# Mainboard.net
KiCad netlist of a schematic drawn in EAGLE
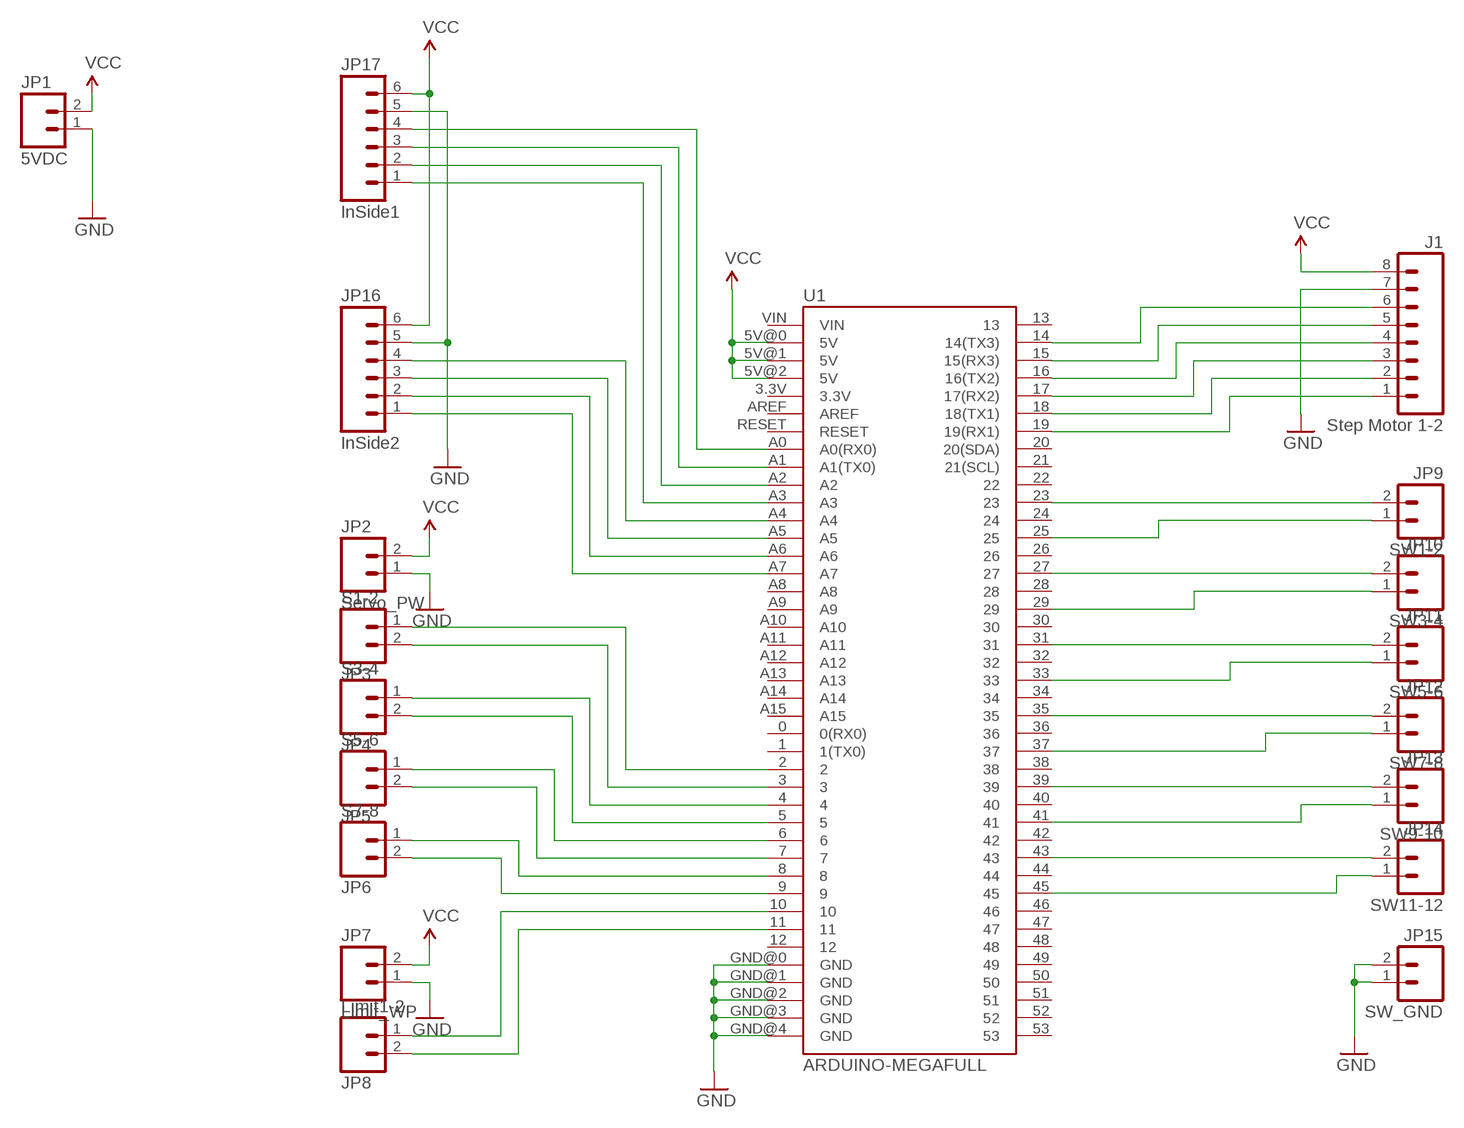
[diagram p0: schematic, sheet 1]

(export (version "E")
  (design (tool "Eeschema 10.0.6"))
  (components
    (comp (ref "J1")
      (value "Step Motor 1-2")
      (footprint "eagle-import:1X08_LONGPADS")
      (libsource (lib "eagle-import") (part "M08LONGPADS"))
    )
    (comp (ref "JP1")
      (value "5VDC")
      (footprint "eagle-import:SCREWTERMINAL-5MM-2")
      (libsource (lib "eagle-import") (part "M025MM"))
    )
    (comp (ref "JP2")
      (value "Servo_PW")
      (footprint "eagle-import:SCREWTERMINAL-5MM-2")
      (libsource (lib "eagle-import") (part "M025MM"))
    )
    (comp (ref "JP3")
      (value "S1-2")
      (footprint "eagle-import:SCREWTERMINAL-5MM-2")
      (libsource (lib "eagle-import") (part "M025MM"))
    )
    (comp (ref "JP4")
      (value "S3-4")
      (footprint "eagle-import:SCREWTERMINAL-5MM-2")
      (libsource (lib "eagle-import") (part "M025MM"))
    )
    (comp (ref "JP5")
      (value "S5-6")
      (footprint "eagle-import:SCREWTERMINAL-5MM-2")
      (libsource (lib "eagle-import") (part "M025MM"))
    )
    (comp (ref "JP6")
      (value "S7-8")
      (footprint "eagle-import:SCREWTERMINAL-5MM-2")
      (libsource (lib "eagle-import") (part "M025MM"))
    )
    (comp (ref "JP7")
      (value "Limit_WP")
      (footprint "eagle-import:SCREWTERMINAL-5MM-2")
      (libsource (lib "eagle-import") (part "M025MM"))
    )
    (comp (ref "JP8")
      (value "Limit1-2")
      (footprint "eagle-import:SCREWTERMINAL-5MM-2")
      (libsource (lib "eagle-import") (part "M025MM"))
    )
    (comp (ref "JP9")
      (value "SW1-2")
      (footprint "eagle-import:SCREWTERMINAL-5MM-2")
      (libsource (lib "eagle-import") (part "M025MM"))
    )
    (comp (ref "JP10")
      (value "SW3-4")
      (footprint "eagle-import:SCREWTERMINAL-5MM-2")
      (libsource (lib "eagle-import") (part "M025MM"))
    )
    (comp (ref "JP11")
      (value "SW5-6")
      (footprint "eagle-import:SCREWTERMINAL-5MM-2")
      (libsource (lib "eagle-import") (part "M025MM"))
    )
    (comp (ref "JP12")
      (value "SW7-8")
      (footprint "eagle-import:SCREWTERMINAL-5MM-2")
      (libsource (lib "eagle-import") (part "M025MM"))
    )
    (comp (ref "JP13")
      (value "SW9-10")
      (footprint "eagle-import:SCREWTERMINAL-5MM-2")
      (libsource (lib "eagle-import") (part "M025MM"))
    )
    (comp (ref "JP14")
      (value "SW11-12")
      (footprint "eagle-import:SCREWTERMINAL-5MM-2")
      (libsource (lib "eagle-import") (part "M025MM"))
    )
    (comp (ref "JP15")
      (value "SW_GND")
      (footprint "eagle-import:SCREWTERMINAL-5MM-2")
      (libsource (lib "eagle-import") (part "M025MM"))
    )
    (comp (ref "JP16")
      (value "InSide2")
      (footprint "eagle-import:1X06_LONGPADS")
      (libsource (lib "eagle-import") (part "M06LONGPADS"))
    )
    (comp (ref "JP17")
      (value "InSide1")
      (footprint "eagle-import:1X06_LONGPADS")
      (libsource (lib "eagle-import") (part "M06LONGPADS"))
    )
    (comp (ref "U1")
      (value "ARDUINO-MEGAFULL")
      (footprint "eagle-import:ARDUINO_MEGA")
      (libsource (lib "eagle-import") (part "ARDUINO-MEGAFULL"))
    )
  )
  (nets
    (net (code "1") (name "GND") (class "Default")
      (node (ref "J1") (pin "7") (pinfunction "7_7") (pintype "passive"))
      (node (ref "JP1") (pin "1") (pinfunction "1_1") (pintype "passive"))
      (node (ref "JP15") (pin "1") (pinfunction "1_1") (pintype "passive"))
      (node (ref "JP15") (pin "2") (pinfunction "2_2") (pintype "passive"))
      (node (ref "JP16") (pin "5") (pinfunction "5_5") (pintype "passive"))
      (node (ref "JP17") (pin "5") (pinfunction "5_5") (pintype "passive"))
      (node (ref "JP2") (pin "1") (pinfunction "1_1") (pintype "passive"))
      (node (ref "JP7") (pin "1") (pinfunction "1_1") (pintype "passive"))
      (node (ref "U1") (pin "GND@0") (pinfunction "GND_GND@0") (pintype "bidirectional"))
      (node (ref "U1") (pin "GND@1") (pinfunction "GND_GND@1") (pintype "bidirectional"))
      (node (ref "U1") (pin "GND@2") (pinfunction "GND_GND@2") (pintype "bidirectional"))
      (node (ref "U1") (pin "GND@3") (pinfunction "GND_GND@3") (pintype "bidirectional"))
      (node (ref "U1") (pin "GND@4") (pinfunction "GND_GND@4") (pintype "bidirectional"))
    )
    (net (code "2") (name "Net-(JP3-Pad1)") (class "Default")
      (node (ref "JP3") (pin "1") (pinfunction "1_1") (pintype "passive"))
      (node (ref "U1") (pin "2") (pinfunction "2_2") (pintype "bidirectional"))
    )
    (net (code "3") (name "Net-(JP3-Pad2)") (class "Default")
      (node (ref "JP3") (pin "2") (pinfunction "2_2") (pintype "passive"))
      (node (ref "U1") (pin "3") (pinfunction "3_3") (pintype "bidirectional"))
    )
    (net (code "4") (name "Net-(JP4-Pad1)") (class "Default")
      (node (ref "JP4") (pin "1") (pinfunction "1_1") (pintype "passive"))
      (node (ref "U1") (pin "4") (pinfunction "4_4") (pintype "bidirectional"))
    )
    (net (code "5") (name "Net-(JP4-Pad2)") (class "Default")
      (node (ref "JP4") (pin "2") (pinfunction "2_2") (pintype "passive"))
      (node (ref "U1") (pin "5") (pinfunction "5_5") (pintype "bidirectional"))
    )
    (net (code "6") (name "Net-(JP5-Pad1)") (class "Default")
      (node (ref "JP5") (pin "1") (pinfunction "1_1") (pintype "passive"))
      (node (ref "U1") (pin "6") (pinfunction "6_6") (pintype "bidirectional"))
    )
    (net (code "7") (name "Net-(JP5-Pad2)") (class "Default")
      (node (ref "JP5") (pin "2") (pinfunction "2_2") (pintype "passive"))
      (node (ref "U1") (pin "7") (pinfunction "7_7") (pintype "bidirectional"))
    )
    (net (code "8") (name "Net-(JP6-Pad1)") (class "Default")
      (node (ref "JP6") (pin "1") (pinfunction "1_1") (pintype "passive"))
      (node (ref "U1") (pin "8") (pinfunction "8_8") (pintype "bidirectional"))
    )
    (net (code "9") (name "Net-(JP6-Pad2)") (class "Default")
      (node (ref "JP6") (pin "2") (pinfunction "2_2") (pintype "passive"))
      (node (ref "U1") (pin "9") (pinfunction "9_9") (pintype "bidirectional"))
    )
    (net (code "10") (name "Net-(JP8-Pad1)") (class "Default")
      (node (ref "JP8") (pin "1") (pinfunction "1_1") (pintype "passive"))
      (node (ref "U1") (pin "10") (pinfunction "10_10") (pintype "bidirectional"))
    )
    (net (code "11") (name "Net-(JP8-Pad2)") (class "Default")
      (node (ref "JP8") (pin "2") (pinfunction "2_2") (pintype "passive"))
      (node (ref "U1") (pin "11") (pinfunction "11_11") (pintype "bidirectional"))
    )
    (net (code "12") (name "Net-(JP9-Pad1)") (class "Default")
      (node (ref "JP9") (pin "1") (pinfunction "1_1") (pintype "passive"))
      (node (ref "U1") (pin "25") (pinfunction "25_25") (pintype "bidirectional"))
    )
    (net (code "13") (name "Net-(JP9-Pad2)") (class "Default")
      (node (ref "JP9") (pin "2") (pinfunction "2_2") (pintype "passive"))
      (node (ref "U1") (pin "23") (pinfunction "23_23") (pintype "bidirectional"))
    )
    (net (code "14") (name "Net-(JP10-Pad1)") (class "Default")
      (node (ref "JP10") (pin "1") (pinfunction "1_1") (pintype "passive"))
      (node (ref "U1") (pin "29") (pinfunction "29_29") (pintype "bidirectional"))
    )
    (net (code "15") (name "Net-(JP10-Pad2)") (class "Default")
      (node (ref "JP10") (pin "2") (pinfunction "2_2") (pintype "passive"))
      (node (ref "U1") (pin "27") (pinfunction "27_27") (pintype "bidirectional"))
    )
    (net (code "16") (name "Net-(JP11-Pad1)") (class "Default")
      (node (ref "JP11") (pin "1") (pinfunction "1_1") (pintype "passive"))
      (node (ref "U1") (pin "33") (pinfunction "33_33") (pintype "bidirectional"))
    )
    (net (code "17") (name "Net-(JP11-Pad2)") (class "Default")
      (node (ref "JP11") (pin "2") (pinfunction "2_2") (pintype "passive"))
      (node (ref "U1") (pin "31") (pinfunction "31_31") (pintype "bidirectional"))
    )
    (net (code "18") (name "Net-(JP12-Pad1)") (class "Default")
      (node (ref "JP12") (pin "1") (pinfunction "1_1") (pintype "passive"))
      (node (ref "U1") (pin "37") (pinfunction "37_37") (pintype "bidirectional"))
    )
    (net (code "19") (name "Net-(JP12-Pad2)") (class "Default")
      (node (ref "JP12") (pin "2") (pinfunction "2_2") (pintype "passive"))
      (node (ref "U1") (pin "35") (pinfunction "35_35") (pintype "bidirectional"))
    )
    (net (code "20") (name "Net-(JP13-Pad1)") (class "Default")
      (node (ref "JP13") (pin "1") (pinfunction "1_1") (pintype "passive"))
      (node (ref "U1") (pin "41") (pinfunction "41_41") (pintype "bidirectional"))
    )
    (net (code "21") (name "Net-(JP13-Pad2)") (class "Default")
      (node (ref "JP13") (pin "2") (pinfunction "2_2") (pintype "passive"))
      (node (ref "U1") (pin "39") (pinfunction "39_39") (pintype "bidirectional"))
    )
    (net (code "22") (name "Net-(JP14-Pad1)") (class "Default")
      (node (ref "JP14") (pin "1") (pinfunction "1_1") (pintype "passive"))
      (node (ref "U1") (pin "45") (pinfunction "45_45") (pintype "bidirectional"))
    )
    (net (code "23") (name "Net-(JP14-Pad2)") (class "Default")
      (node (ref "JP14") (pin "2") (pinfunction "2_2") (pintype "passive"))
      (node (ref "U1") (pin "43") (pinfunction "43_43") (pintype "bidirectional"))
    )
    (net (code "24") (name "Net-(JP16-Pad1)") (class "Default")
      (node (ref "JP16") (pin "1") (pinfunction "1_1") (pintype "passive"))
      (node (ref "U1") (pin "A7") (pinfunction "A7_A7") (pintype "bidirectional"))
    )
    (net (code "25") (name "Net-(JP16-Pad2)") (class "Default")
      (node (ref "JP16") (pin "2") (pinfunction "2_2") (pintype "passive"))
      (node (ref "U1") (pin "A6") (pinfunction "A6_A6") (pintype "bidirectional"))
    )
    (net (code "26") (name "Net-(JP16-Pad3)") (class "Default")
      (node (ref "JP16") (pin "3") (pinfunction "3_3") (pintype "passive"))
      (node (ref "U1") (pin "A5") (pinfunction "A5_A5") (pintype "bidirectional"))
    )
    (net (code "27") (name "Net-(JP16-Pad4)") (class "Default")
      (node (ref "JP16") (pin "4") (pinfunction "4_4") (pintype "passive"))
      (node (ref "U1") (pin "A4") (pinfunction "A4_A4") (pintype "bidirectional"))
    )
    (net (code "28") (name "Net-(JP17-Pad1)") (class "Default")
      (node (ref "JP17") (pin "1") (pinfunction "1_1") (pintype "passive"))
      (node (ref "U1") (pin "A3") (pinfunction "A3_A3") (pintype "bidirectional"))
    )
    (net (code "29") (name "Net-(JP17-Pad2)") (class "Default")
      (node (ref "JP17") (pin "2") (pinfunction "2_2") (pintype "passive"))
      (node (ref "U1") (pin "A2") (pinfunction "A2_A2") (pintype "bidirectional"))
    )
    (net (code "30") (name "Net-(U1-14(TX3))") (class "Default")
      (node (ref "J1") (pin "6") (pinfunction "6_6") (pintype "passive"))
      (node (ref "U1") (pin "14") (pinfunction "14(TX3)_14") (pintype "bidirectional"))
    )
    (net (code "31") (name "Net-(U1-15(RX3))") (class "Default")
      (node (ref "J1") (pin "5") (pinfunction "5_5") (pintype "passive"))
      (node (ref "U1") (pin "15") (pinfunction "15(RX3)_15") (pintype "bidirectional"))
    )
    (net (code "32") (name "Net-(U1-16(TX2))") (class "Default")
      (node (ref "J1") (pin "4") (pinfunction "4_4") (pintype "passive"))
      (node (ref "U1") (pin "16") (pinfunction "16(TX2)_16") (pintype "bidirectional"))
    )
    (net (code "33") (name "Net-(U1-17(RX2))") (class "Default")
      (node (ref "J1") (pin "3") (pinfunction "3_3") (pintype "passive"))
      (node (ref "U1") (pin "17") (pinfunction "17(RX2)_17") (pintype "bidirectional"))
    )
    (net (code "34") (name "Net-(U1-18(TX1))") (class "Default")
      (node (ref "J1") (pin "2") (pinfunction "2_2") (pintype "passive"))
      (node (ref "U1") (pin "18") (pinfunction "18(TX1)_18") (pintype "bidirectional"))
    )
    (net (code "35") (name "Net-(U1-19(RX1))") (class "Default")
      (node (ref "J1") (pin "1") (pinfunction "1_1") (pintype "passive"))
      (node (ref "U1") (pin "19") (pinfunction "19(RX1)_19") (pintype "bidirectional"))
    )
    (net (code "36") (name "Net-(U1-A0(RX0))") (class "Default")
      (node (ref "JP17") (pin "4") (pinfunction "4_4") (pintype "passive"))
      (node (ref "U1") (pin "A0") (pinfunction "A0(RX0)_A0") (pintype "bidirectional"))
    )
    (net (code "37") (name "Net-(U1-A1(TX0))") (class "Default")
      (node (ref "JP17") (pin "3") (pinfunction "3_3") (pintype "passive"))
      (node (ref "U1") (pin "A1") (pinfunction "A1(TX0)_A1") (pintype "bidirectional"))
    )
    (net (code "38") (name "VCC") (class "Default")
      (node (ref "J1") (pin "8") (pinfunction "8_8") (pintype "passive"))
      (node (ref "JP1") (pin "2") (pinfunction "2_2") (pintype "passive"))
      (node (ref "JP16") (pin "6") (pinfunction "6_6") (pintype "passive"))
      (node (ref "JP17") (pin "6") (pinfunction "6_6") (pintype "passive"))
      (node (ref "JP2") (pin "2") (pinfunction "2_2") (pintype "passive"))
      (node (ref "JP7") (pin "2") (pinfunction "2_2") (pintype "passive"))
      (node (ref "U1") (pin "5V@0") (pinfunction "5V_5V@0") (pintype "bidirectional"))
      (node (ref "U1") (pin "5V@1") (pinfunction "5V_5V@1") (pintype "bidirectional"))
      (node (ref "U1") (pin "5V@2") (pinfunction "5V_5V@2") (pintype "bidirectional"))
    )
    (net (code "39") (name "unconnected-(U1-0(RX0)-Pad0)") (class "Default")
      (node (ref "U1") (pin "0") (pinfunction "0(RX0)_0") (pintype "bidirectional"))
    )
    (net (code "40") (name "unconnected-(U1-1(TX0)-Pad1)") (class "Default")
      (node (ref "U1") (pin "1") (pinfunction "1(TX0)_1") (pintype "bidirectional"))
    )
    (net (code "41") (name "unconnected-(U1-20(SDA)-Pad20)") (class "Default")
      (node (ref "U1") (pin "20") (pinfunction "20(SDA)_20") (pintype "bidirectional"))
    )
    (net (code "42") (name "unconnected-(U1-21(SCL)-Pad21)") (class "Default")
      (node (ref "U1") (pin "21") (pinfunction "21(SCL)_21") (pintype "bidirectional"))
    )
    (net (code "43") (name "unconnected-(U1-Pad3.3V)") (class "Default")
      (node (ref "U1") (pin "3.3V") (pinfunction "3.3V_3.3V") (pintype "bidirectional"))
    )
    (net (code "44") (name "unconnected-(U1-Pad12)") (class "Default")
      (node (ref "U1") (pin "12") (pinfunction "12_12") (pintype "bidirectional"))
    )
    (net (code "45") (name "unconnected-(U1-Pad13)") (class "Default")
      (node (ref "U1") (pin "13") (pinfunction "13_13") (pintype "bidirectional"))
    )
    (net (code "46") (name "unconnected-(U1-Pad22)") (class "Default")
      (node (ref "U1") (pin "22") (pinfunction "22_22") (pintype "bidirectional"))
    )
    (net (code "47") (name "unconnected-(U1-Pad24)") (class "Default")
      (node (ref "U1") (pin "24") (pinfunction "24_24") (pintype "bidirectional"))
    )
    (net (code "48") (name "unconnected-(U1-Pad26)") (class "Default")
      (node (ref "U1") (pin "26") (pinfunction "26_26") (pintype "bidirectional"))
    )
    (net (code "49") (name "unconnected-(U1-Pad28)") (class "Default")
      (node (ref "U1") (pin "28") (pinfunction "28_28") (pintype "bidirectional"))
    )
    (net (code "50") (name "unconnected-(U1-Pad30)") (class "Default")
      (node (ref "U1") (pin "30") (pinfunction "30_30") (pintype "bidirectional"))
    )
    (net (code "51") (name "unconnected-(U1-Pad32)") (class "Default")
      (node (ref "U1") (pin "32") (pinfunction "32_32") (pintype "bidirectional"))
    )
    (net (code "52") (name "unconnected-(U1-Pad34)") (class "Default")
      (node (ref "U1") (pin "34") (pinfunction "34_34") (pintype "bidirectional"))
    )
    (net (code "53") (name "unconnected-(U1-Pad36)") (class "Default")
      (node (ref "U1") (pin "36") (pinfunction "36_36") (pintype "bidirectional"))
    )
    (net (code "54") (name "unconnected-(U1-Pad38)") (class "Default")
      (node (ref "U1") (pin "38") (pinfunction "38_38") (pintype "bidirectional"))
    )
    (net (code "55") (name "unconnected-(U1-Pad40)") (class "Default")
      (node (ref "U1") (pin "40") (pinfunction "40_40") (pintype "bidirectional"))
    )
    (net (code "56") (name "unconnected-(U1-Pad42)") (class "Default")
      (node (ref "U1") (pin "42") (pinfunction "42_42") (pintype "bidirectional"))
    )
    (net (code "57") (name "unconnected-(U1-Pad44)") (class "Default")
      (node (ref "U1") (pin "44") (pinfunction "44_44") (pintype "bidirectional"))
    )
    (net (code "58") (name "unconnected-(U1-Pad46)") (class "Default")
      (node (ref "U1") (pin "46") (pinfunction "46_46") (pintype "bidirectional"))
    )
    (net (code "59") (name "unconnected-(U1-Pad47)") (class "Default")
      (node (ref "U1") (pin "47") (pinfunction "47_47") (pintype "bidirectional"))
    )
    (net (code "60") (name "unconnected-(U1-Pad48)") (class "Default")
      (node (ref "U1") (pin "48") (pinfunction "48_48") (pintype "bidirectional"))
    )
    (net (code "61") (name "unconnected-(U1-Pad49)") (class "Default")
      (node (ref "U1") (pin "49") (pinfunction "49_49") (pintype "bidirectional"))
    )
    (net (code "62") (name "unconnected-(U1-Pad50)") (class "Default")
      (node (ref "U1") (pin "50") (pinfunction "50_50") (pintype "bidirectional"))
    )
    (net (code "63") (name "unconnected-(U1-Pad51)") (class "Default")
      (node (ref "U1") (pin "51") (pinfunction "51_51") (pintype "bidirectional"))
    )
    (net (code "64") (name "unconnected-(U1-Pad52)") (class "Default")
      (node (ref "U1") (pin "52") (pinfunction "52_52") (pintype "bidirectional"))
    )
    (net (code "65") (name "unconnected-(U1-Pad53)") (class "Default")
      (node (ref "U1") (pin "53") (pinfunction "53_53") (pintype "bidirectional"))
    )
    (net (code "66") (name "unconnected-(U1-PadA8)") (class "Default")
      (node (ref "U1") (pin "A8") (pinfunction "A8_A8") (pintype "bidirectional"))
    )
    (net (code "67") (name "unconnected-(U1-PadA9)") (class "Default")
      (node (ref "U1") (pin "A9") (pinfunction "A9_A9") (pintype "bidirectional"))
    )
    (net (code "68") (name "unconnected-(U1-PadA10)") (class "Default")
      (node (ref "U1") (pin "A10") (pinfunction "A10_A10") (pintype "bidirectional"))
    )
    (net (code "69") (name "unconnected-(U1-PadA11)") (class "Default")
      (node (ref "U1") (pin "A11") (pinfunction "A11_A11") (pintype "bidirectional"))
    )
    (net (code "70") (name "unconnected-(U1-PadA12)") (class "Default")
      (node (ref "U1") (pin "A12") (pinfunction "A12_A12") (pintype "bidirectional"))
    )
    (net (code "71") (name "unconnected-(U1-PadA13)") (class "Default")
      (node (ref "U1") (pin "A13") (pinfunction "A13_A13") (pintype "bidirectional"))
    )
    (net (code "72") (name "unconnected-(U1-PadA14)") (class "Default")
      (node (ref "U1") (pin "A14") (pinfunction "A14_A14") (pintype "bidirectional"))
    )
    (net (code "73") (name "unconnected-(U1-PadA15)") (class "Default")
      (node (ref "U1") (pin "A15") (pinfunction "A15_A15") (pintype "bidirectional"))
    )
    (net (code "74") (name "unconnected-(U1-PadAREF)") (class "Default")
      (node (ref "U1") (pin "AREF") (pinfunction "AREF_AREF") (pintype "bidirectional"))
    )
    (net (code "75") (name "unconnected-(U1-PadRESET)") (class "Default")
      (node (ref "U1") (pin "RESET") (pinfunction "RESET_RESET") (pintype "bidirectional"))
    )
    (net (code "76") (name "unconnected-(U1-PadVIN)") (class "Default")
      (node (ref "U1") (pin "VIN") (pinfunction "VIN_VIN") (pintype "bidirectional"))
    )
  )
)
